# powerV2.net
KiCad netlist of a schematic drawn in EAGLE
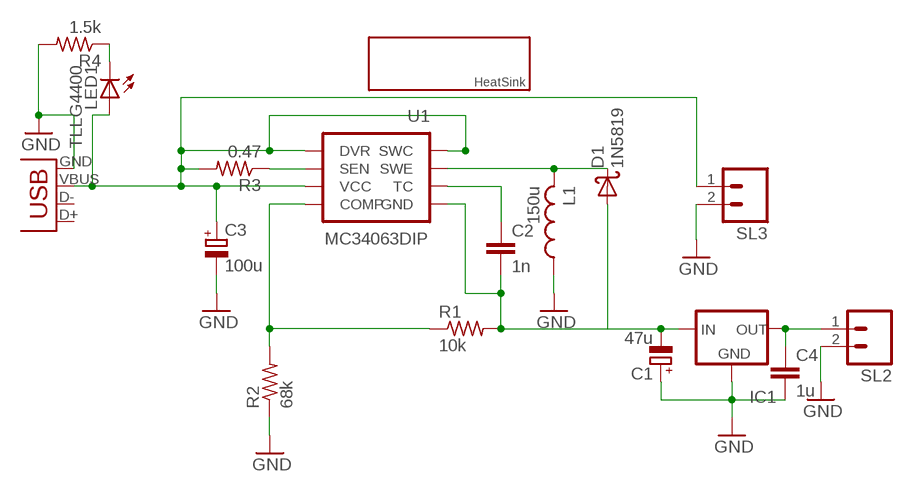
[diagram p0: schematic, sheet 1]

(export (version "E")
  (design (tool "Eeschema 10.0.6"))
  (components
    (comp (ref "C1")
      (value "47u")
      (footprint "eagle-import:E2,5-7")
      (libsource (lib "eagle-import") (part "CPOL-EUE2.5-7"))
    )
    (comp (ref "C2")
      (value "1n")
      (footprint "eagle-import:C025-024X044")
      (libsource (lib "eagle-import") (part "C-EU025-024X044"))
    )
    (comp (ref "C3")
      (value "100u")
      (footprint "eagle-import:E2,5-7")
      (libsource (lib "eagle-import") (part "CPOL-EUE2.5-7"))
    )
    (comp (ref "C4")
      (value "1u")
      (footprint "eagle-import:C025-024X044")
      (libsource (lib "eagle-import") (part "C-EU025-024X044"))
    )
    (comp (ref "D1")
      (value "1N5819")
      (footprint "eagle-import:DO41-10")
      (libsource (lib "eagle-import") (part "1N5819"))
    )
    (comp (ref "IC1")
      (value "79XXS")
      (footprint "eagle-import:79XXS")
      (libsource (lib "eagle-import") (part "79XXS"))
    )
    (comp (ref "L1")
      (value "150u")
      (footprint "eagle-import:0204_7")
      (libsource (lib "eagle-import") (part "L-US0204/7"))
    )
    (comp (ref "LED1")
      (value "TLLG4400")
      (footprint "eagle-import:LED3MM")
      (fields (field (name "MF") "VISHAY SEMICONDUCTOR"))
      (libsource (lib "eagle-import") (part "TLLG4400"))
    )
    (comp (ref "R1")
      (value "10k")
      (footprint "eagle-import:0204_7")
      (libsource (lib "eagle-import") (part "R-US_0204/7"))
    )
    (comp (ref "R2")
      (value "68k")
      (footprint "eagle-import:0204_7")
      (libsource (lib "eagle-import") (part "R-US_0204/7"))
    )
    (comp (ref "R3")
      (value "0.47")
      (footprint "eagle-import:P0613_15")
      (libsource (lib "eagle-import") (part "R-US_0613/15"))
    )
    (comp (ref "R4")
      (value "1.5k")
      (footprint "eagle-import:0204_7")
      (libsource (lib "eagle-import") (part "R-US_0204/7"))
    )
    (comp (ref "SL2")
      (value "M02")
      (footprint "eagle-import:02P")
      (libsource (lib "eagle-import") (part "M02"))
    )
    (comp (ref "SL3")
      (value "M02")
      (footprint "eagle-import:02P")
      (libsource (lib "eagle-import") (part "M02"))
    )
    (comp (ref "U$1")
      (value "HEATSINKMEDIUM")
      (footprint "eagle-import:HEATSINK-MED")
      (libsource (lib "eagle-import") (part "HEATSINKMEDIUM"))
    )
    (comp (ref "U1")
      (value "MC34063DIP")
      (footprint "eagle-import:DIP-08")
      (libsource (lib "eagle-import") (part "MC34063DIP"))
    )
    (comp (ref "X1")
      (value "USBSMD")
      (footprint "eagle-import:USB-MINIB")
      (libsource (lib "eagle-import") (part "USBSMD"))
    )
  )
  (nets
    (net (code "1") (name "GND") (class "Default")
      (node (ref "C1") (pin "+") (pinfunction "+_+") (pintype "passive"))
      (node (ref "C3") (pin "-") (pinfunction "-_-") (pintype "passive"))
      (node (ref "C4") (pin "2") (pinfunction "2_2") (pintype "passive"))
      (node (ref "IC1") (pin "GND") (pinfunction "GND_GND") (pintype "input"))
      (node (ref "L1") (pin "1") (pinfunction "1_1") (pintype "passive"))
      (node (ref "R2") (pin "1") (pinfunction "1_1") (pintype "passive"))
      (node (ref "R4") (pin "2") (pinfunction "2_2") (pintype "passive"))
      (node (ref "SL2") (pin "2") (pinfunction "2_2") (pintype "passive"))
      (node (ref "SL3") (pin "2") (pinfunction "2_2") (pintype "passive"))
      (node (ref "X1") (pin "GND") (pinfunction "GND_GND") (pintype "bidirectional"))
    )
    (net (code "2") (name "Net-(C4-Pad1)") (class "Default")
      (node (ref "C4") (pin "1") (pinfunction "1_1") (pintype "passive"))
      (node (ref "IC1") (pin "OUT") (pinfunction "OUT_OUT") (pintype "passive"))
      (node (ref "SL2") (pin "1") (pinfunction "1_1") (pintype "passive"))
    )
    (net (code "3") (name "Net-(LED1-C)") (class "Default")
      (node (ref "LED1") (pin "K") (pinfunction "C_K") (pintype "passive"))
      (node (ref "R4") (pin "1") (pinfunction "1_1") (pintype "passive"))
    )
    (net (code "4") (name "Net-(U1-COMP)") (class "Default")
      (node (ref "R1") (pin "1") (pinfunction "1_1") (pintype "passive"))
      (node (ref "R2") (pin "2") (pinfunction "2_2") (pintype "passive"))
      (node (ref "U1") (pin "5") (pinfunction "COMP_5") (pintype "bidirectional"))
    )
    (net (code "5") (name "Net-(U1-DVR)") (class "Default")
      (node (ref "C3") (pin "+") (pinfunction "+_+") (pintype "passive"))
      (node (ref "LED1") (pin "A") (pinfunction "A_A") (pintype "passive"))
      (node (ref "R3") (pin "2") (pinfunction "2_2") (pintype "passive"))
      (node (ref "SL3") (pin "1") (pinfunction "1_1") (pintype "passive"))
      (node (ref "U1") (pin "1") (pinfunction "SWC_1") (pintype "bidirectional"))
      (node (ref "U1") (pin "6") (pinfunction "VCC_6") (pintype "bidirectional"))
      (node (ref "U1") (pin "8") (pinfunction "DVR_8") (pintype "bidirectional"))
      (node (ref "X1") (pin "VBUS") (pinfunction "VBUS_VBUS") (pintype "bidirectional"))
    )
    (net (code "6") (name "Net-(U1-GND)") (class "Default")
      (node (ref "C1") (pin "-") (pinfunction "-_-") (pintype "passive"))
      (node (ref "C2") (pin "2") (pinfunction "2_2") (pintype "passive"))
      (node (ref "D1") (pin "A") (pinfunction "A_A") (pintype "passive"))
      (node (ref "IC1") (pin "IN") (pinfunction "IN_IN") (pintype "input"))
      (node (ref "R1") (pin "2") (pinfunction "2_2") (pintype "passive"))
      (node (ref "U1") (pin "4") (pinfunction "GND_4") (pintype "bidirectional"))
    )
    (net (code "7") (name "Net-(U1-SEN)") (class "Default")
      (node (ref "R3") (pin "1") (pinfunction "1_1") (pintype "passive"))
      (node (ref "U1") (pin "7") (pinfunction "SEN_7") (pintype "bidirectional"))
    )
    (net (code "8") (name "Net-(U1-SWE)") (class "Default")
      (node (ref "D1") (pin "C") (pinfunction "C_C") (pintype "passive"))
      (node (ref "L1") (pin "2") (pinfunction "2_2") (pintype "passive"))
      (node (ref "U1") (pin "2") (pinfunction "SWE_2") (pintype "bidirectional"))
    )
    (net (code "9") (name "Net-(U1-TC)") (class "Default")
      (node (ref "C2") (pin "1") (pinfunction "1_1") (pintype "passive"))
      (node (ref "U1") (pin "3") (pinfunction "TC_3") (pintype "bidirectional"))
    )
    (net (code "10") (name "unconnected-(X1-PadD+)") (class "Default")
      (node (ref "X1") (pin "D+") (pinfunction "D+_D+") (pintype "bidirectional"))
    )
    (net (code "11") (name "unconnected-(X1-PadD-)") (class "Default")
      (node (ref "X1") (pin "D-") (pinfunction "D-_D-") (pintype "bidirectional"))
    )
  )
)
